# sch1.net
KiCad netlist of a schematic drawn in EAGLE
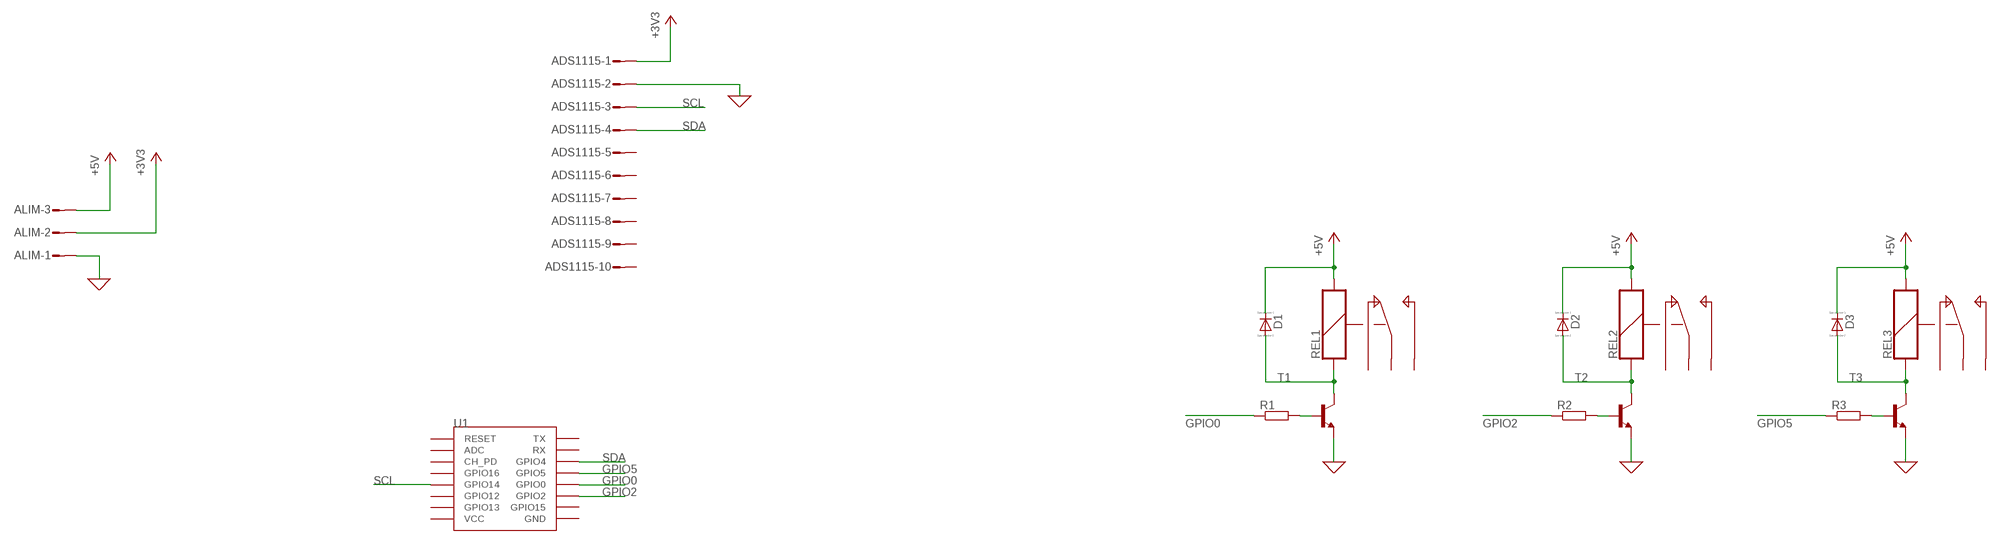
[diagram p0: schematic, sheet 1]

(export (version "E")
  (design (tool "Eeschema 10.0.6"))
  (components
    (comp (ref "ADS1115")
      (value "S10P")
      (footprint "eagle-import:S10P")
      (libsource (lib "eagle-import") (part "S10P"))
    )
    (comp (ref "ALIM")
      (value "S03P")
      (footprint "eagle-import:S03P")
      (libsource (lib "eagle-import") (part "S03P"))
    )
    (comp (ref "D1")
      (value "DIODE_E-")
      (footprint "eagle-import:DIODE_SMB")
      (libsource (lib "eagle-import") (part "DIODE_E-"))
    )
    (comp (ref "D2")
      (value "DIODE_E-")
      (footprint "eagle-import:DIODE_SMB")
      (libsource (lib "eagle-import") (part "DIODE_E-"))
    )
    (comp (ref "D3")
      (value "DIODE_E-")
      (footprint "eagle-import:DIODE_SMB")
      (libsource (lib "eagle-import") (part "DIODE_E-"))
    )
    (comp (ref "R1")
      (value "R-EU_M0805")
      (footprint "eagle-import:M0805")
      (libsource (lib "eagle-import") (part "R-EU_M0805"))
    )
    (comp (ref "R2")
      (value "R-EU_M0805")
      (footprint "eagle-import:M0805")
      (libsource (lib "eagle-import") (part "R-EU_M0805"))
    )
    (comp (ref "R3")
      (value "R-EU_M0805")
      (footprint "eagle-import:M0805")
      (libsource (lib "eagle-import") (part "R-EU_M0805"))
    )
    (comp (ref "REL1")
      (value "REL-5PIN")
      (footprint "eagle-import:REL-5PIN")
      (libsource (lib "eagle-import") (part "REL-5PIN"))
    )
    (comp (ref "REL2")
      (value "REL-5PIN")
      (footprint "eagle-import:REL-5PIN")
      (libsource (lib "eagle-import") (part "REL-5PIN"))
    )
    (comp (ref "REL3")
      (value "REL-5PIN")
      (footprint "eagle-import:REL-5PIN")
      (libsource (lib "eagle-import") (part "REL-5PIN"))
    )
    (comp (ref "T1")
      (value "BC817-NPN-SOT23-BEC")
      (footprint "eagle-import:SOT23-BEC")
      (libsource (lib "eagle-import") (part "-NPN-SOT23-BECBC817"))
    )
    (comp (ref "T2")
      (value "BC817-NPN-SOT23-BEC")
      (footprint "eagle-import:SOT23-BEC")
      (libsource (lib "eagle-import") (part "-NPN-SOT23-BECBC817"))
    )
    (comp (ref "T3")
      (value "BC817-NPN-SOT23-BEC")
      (footprint "eagle-import:SOT23-BEC")
      (libsource (lib "eagle-import") (part "-NPN-SOT23-BECBC817"))
    )
    (comp (ref "U1")
      (value "ESP12SMD")
      (footprint "eagle-import:ESP12-SMD")
      (libsource (lib "eagle-import") (part "ESP12SMD"))
    )
  )
  (nets
    (net (code "1") (name "+3V3") (class "Default")
      (node (ref "ADS1115") (pin "1") (pinfunction "S_1") (pintype "passive"))
      (node (ref "ALIM") (pin "2") (pinfunction "S_2") (pintype "passive"))
    )
    (net (code "2") (name "+5V") (class "Default")
      (node (ref "ALIM") (pin "3") (pinfunction "S_3") (pintype "passive"))
      (node (ref "D1") (pin "C") (pinfunction "A_C") (pintype "passive"))
      (node (ref "D2") (pin "C") (pinfunction "A_C") (pintype "passive"))
      (node (ref "D3") (pin "C") (pinfunction "A_C") (pintype "passive"))
      (node (ref "REL1") (pin "S2") (pinfunction "S2_S2") (pintype "passive"))
      (node (ref "REL2") (pin "S2") (pinfunction "S2_S2") (pintype "passive"))
      (node (ref "REL3") (pin "S2") (pinfunction "S2_S2") (pintype "passive"))
    )
    (net (code "3") (name "/GPIO0") (class "Default")
      (node (ref "R1") (pin "1") (pinfunction "1_1") (pintype "passive"))
      (node (ref "U1") (pin "GPIO0") (pinfunction "GPIO0_GPIO0") (pintype "bidirectional"))
    )
    (net (code "4") (name "/GPIO2") (class "Default")
      (node (ref "R2") (pin "1") (pinfunction "1_1") (pintype "passive"))
      (node (ref "U1") (pin "GPIO2") (pinfunction "GPIO2_GPIO2") (pintype "bidirectional"))
    )
    (net (code "5") (name "/GPIO5") (class "Default")
      (node (ref "R3") (pin "1") (pinfunction "1_1") (pintype "passive"))
      (node (ref "U1") (pin "GPIO5") (pinfunction "GPIO5_GPIO5") (pintype "bidirectional"))
    )
    (net (code "6") (name "/SCL") (class "Default")
      (node (ref "ADS1115") (pin "3") (pinfunction "S_3") (pintype "passive"))
      (node (ref "U1") (pin "GPIO14") (pinfunction "GPIO14_GPIO14") (pintype "bidirectional"))
    )
    (net (code "7") (name "/SDA") (class "Default")
      (node (ref "ADS1115") (pin "4") (pinfunction "S_4") (pintype "passive"))
      (node (ref "U1") (pin "GPIO4") (pinfunction "GPIO4_GPIO4") (pintype "bidirectional"))
    )
    (net (code "8") (name "GND") (class "Default")
      (node (ref "ADS1115") (pin "2") (pinfunction "S_2") (pintype "passive"))
      (node (ref "ALIM") (pin "1") (pinfunction "S_1") (pintype "passive"))
      (node (ref "T1") (pin "E") (pinfunction "E_E") (pintype "passive"))
      (node (ref "T2") (pin "E") (pinfunction "E_E") (pintype "passive"))
      (node (ref "T3") (pin "E") (pinfunction "E_E") (pintype "passive"))
    )
    (net (code "9") (name "Net-(D1-C)") (class "Default")
      (node (ref "D1") (pin "A") (pinfunction "C_A") (pintype "passive"))
      (node (ref "REL1") (pin "S1") (pinfunction "S1_S1") (pintype "passive"))
      (node (ref "T1") (pin "C") (pinfunction "C_C") (pintype "passive"))
    )
    (net (code "10") (name "Net-(D2-C)") (class "Default")
      (node (ref "D2") (pin "A") (pinfunction "C_A") (pintype "passive"))
      (node (ref "REL2") (pin "S1") (pinfunction "S1_S1") (pintype "passive"))
      (node (ref "T2") (pin "C") (pinfunction "C_C") (pintype "passive"))
    )
    (net (code "11") (name "Net-(D3-C)") (class "Default")
      (node (ref "D3") (pin "A") (pinfunction "C_A") (pintype "passive"))
      (node (ref "REL3") (pin "S1") (pinfunction "S1_S1") (pintype "passive"))
      (node (ref "T3") (pin "C") (pinfunction "C_C") (pintype "passive"))
    )
    (net (code "12") (name "Net-(R1-Pad2)") (class "Default")
      (node (ref "R1") (pin "2") (pinfunction "2_2") (pintype "passive"))
      (node (ref "T1") (pin "B") (pinfunction "B_B") (pintype "passive"))
    )
    (net (code "13") (name "Net-(R2-Pad2)") (class "Default")
      (node (ref "R2") (pin "2") (pinfunction "2_2") (pintype "passive"))
      (node (ref "T2") (pin "B") (pinfunction "B_B") (pintype "passive"))
    )
    (net (code "14") (name "Net-(R3-Pad2)") (class "Default")
      (node (ref "R3") (pin "2") (pinfunction "2_2") (pintype "passive"))
      (node (ref "T3") (pin "B") (pinfunction "B_B") (pintype "passive"))
    )
    (net (code "15") (name "unconnected-(ADS1115B-S-Pad10)") (class "Default")
      (node (ref "ADS1115") (pin "10") (pinfunction "S_10") (pintype "passive"))
    )
    (net (code "16") (name "unconnected-(ADS1115F-S-Pad5)") (class "Default")
      (node (ref "ADS1115") (pin "5") (pinfunction "S_5") (pintype "passive"))
    )
    (net (code "17") (name "unconnected-(ADS1115G-S-Pad6)") (class "Default")
      (node (ref "ADS1115") (pin "6") (pinfunction "S_6") (pintype "passive"))
    )
    (net (code "18") (name "unconnected-(ADS1115H-S-Pad7)") (class "Default")
      (node (ref "ADS1115") (pin "7") (pinfunction "S_7") (pintype "passive"))
    )
    (net (code "19") (name "unconnected-(ADS1115I-S-Pad8)") (class "Default")
      (node (ref "ADS1115") (pin "8") (pinfunction "S_8") (pintype "passive"))
    )
    (net (code "20") (name "unconnected-(ADS1115J-S-Pad9)") (class "Default")
      (node (ref "ADS1115") (pin "9") (pinfunction "S_9") (pintype "passive"))
    )
    (net (code "21") (name "unconnected-(REL1-PadC)") (class "Default")
      (node (ref "REL1") (pin "C") (pinfunction "C_C") (pintype "passive"))
    )
    (net (code "22") (name "unconnected-(REL1-PadO)") (class "Default")
      (node (ref "REL1") (pin "O") (pinfunction "O_O") (pintype "passive"))
    )
    (net (code "23") (name "unconnected-(REL1-PadS)") (class "Default")
      (node (ref "REL1") (pin "S") (pinfunction "S_S") (pintype "passive"))
    )
    (net (code "24") (name "unconnected-(REL2-PadC)") (class "Default")
      (node (ref "REL2") (pin "C") (pinfunction "C_C") (pintype "passive"))
    )
    (net (code "25") (name "unconnected-(REL2-PadO)") (class "Default")
      (node (ref "REL2") (pin "O") (pinfunction "O_O") (pintype "passive"))
    )
    (net (code "26") (name "unconnected-(REL2-PadS)") (class "Default")
      (node (ref "REL2") (pin "S") (pinfunction "S_S") (pintype "passive"))
    )
    (net (code "27") (name "unconnected-(REL3-PadC)") (class "Default")
      (node (ref "REL3") (pin "C") (pinfunction "C_C") (pintype "passive"))
    )
    (net (code "28") (name "unconnected-(REL3-PadO)") (class "Default")
      (node (ref "REL3") (pin "O") (pinfunction "O_O") (pintype "passive"))
    )
    (net (code "29") (name "unconnected-(REL3-PadS)") (class "Default")
      (node (ref "REL3") (pin "S") (pinfunction "S_S") (pintype "passive"))
    )
    (net (code "30") (name "unconnected-(U1-PadADC)") (class "Default")
      (node (ref "U1") (pin "ADC") (pinfunction "ADC_ADC") (pintype "bidirectional"))
    )
    (net (code "31") (name "unconnected-(U1-PadCH_PD)") (class "Default")
      (node (ref "U1") (pin "CH_PD") (pinfunction "CH_PD_CH_PD") (pintype "bidirectional"))
    )
    (net (code "32") (name "unconnected-(U1-PadGND)") (class "Default")
      (node (ref "U1") (pin "GND") (pinfunction "GND_GND") (pintype "bidirectional"))
    )
    (net (code "33") (name "unconnected-(U1-PadGPIO12)") (class "Default")
      (node (ref "U1") (pin "GPIO12") (pinfunction "GPIO12_GPIO12") (pintype "bidirectional"))
    )
    (net (code "34") (name "unconnected-(U1-PadGPIO13)") (class "Default")
      (node (ref "U1") (pin "GPIO13") (pinfunction "GPIO13_GPIO13") (pintype "bidirectional"))
    )
    (net (code "35") (name "unconnected-(U1-PadGPIO15)") (class "Default")
      (node (ref "U1") (pin "GPIO15") (pinfunction "GPIO15_GPIO15") (pintype "bidirectional"))
    )
    (net (code "36") (name "unconnected-(U1-PadGPIO16)") (class "Default")
      (node (ref "U1") (pin "GPIO16") (pinfunction "GPIO16_GPIO16") (pintype "bidirectional"))
    )
    (net (code "37") (name "unconnected-(U1-PadRESET)") (class "Default")
      (node (ref "U1") (pin "RESET") (pinfunction "RESET_RESET") (pintype "bidirectional"))
    )
    (net (code "38") (name "unconnected-(U1-PadVCC)") (class "Default")
      (node (ref "U1") (pin "VCC") (pinfunction "VCC_VCC") (pintype "bidirectional"))
    )
    (net (code "39") (name "unconnected-(U1-RX-PadRXD0)") (class "Default")
      (node (ref "U1") (pin "RXD0") (pinfunction "RX_RXD0") (pintype "bidirectional"))
    )
    (net (code "40") (name "unconnected-(U1-TX-PadTXD0)") (class "Default")
      (node (ref "U1") (pin "TXD0") (pinfunction "TX_TXD0") (pintype "bidirectional"))
    )
  )
)
